# IN-12_Module.net
KiCad netlist of a schematic drawn in EAGLE
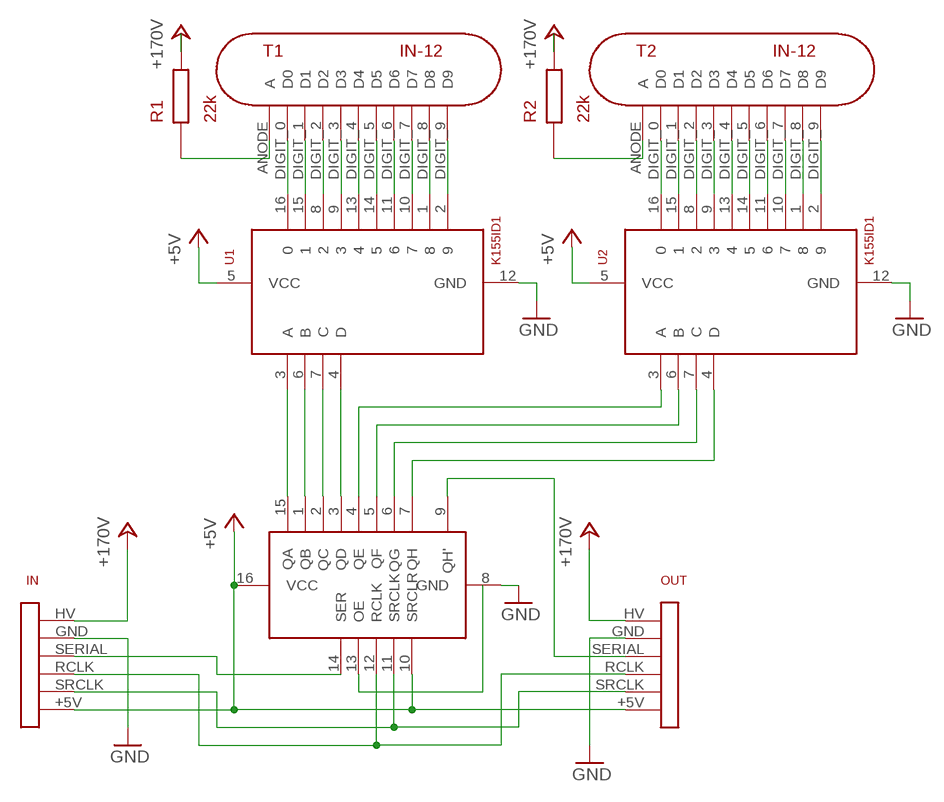
[diagram p0: schematic, sheet 1]

(export (version "E")
  (design (tool "Eeschema 10.0.6"))
  (components
    (comp (ref "IN")
      (value "NIXIE_INTERCONNECT")
      (footprint "eagle-import:NIXIE_INTERCONNECT")
      (libsource (lib "eagle-import") (part "NIXIE_INTERCONNECT"))
    )
    (comp (ref "OUT")
      (value "NIXIE_INTERCONNECT")
      (footprint "eagle-import:NIXIE_INTERCONNECT")
      (libsource (lib "eagle-import") (part "NIXIE_INTERCONNECT"))
    )
    (comp (ref "R1")
      (value "22k")
      (footprint "eagle-import:ANODE_RESISTOR")
      (libsource (lib "eagle-import") (part "ANODE_RESISTOR"))
    )
    (comp (ref "R2")
      (value "22k")
      (footprint "eagle-import:ANODE_RESISTOR")
      (libsource (lib "eagle-import") (part "ANODE_RESISTOR"))
    )
    (comp (ref "T1")
      (value "IN-12")
      (footprint "eagle-import:IN-12")
      (libsource (lib "eagle-import") (part "IN-12"))
    )
    (comp (ref "T2")
      (value "IN-12")
      (footprint "eagle-import:IN-12")
      (libsource (lib "eagle-import") (part "IN-12"))
    )
    (comp (ref "U1")
      (value "K155ID1")
      (footprint "eagle-import:DIP16-2.54-19.2X7.62MM")
      (libsource (lib "eagle-import") (part "K155ID1"))
    )
    (comp (ref "U2")
      (value "K155ID1")
      (footprint "eagle-import:DIP16-2.54-19.2X7.62MM")
      (libsource (lib "eagle-import") (part "K155ID1"))
    )
    (comp (ref "U3")
      (value "74HC595")
      (footprint "eagle-import:DIL16")
      (libsource (lib "eagle-import") (part "74HC595"))
    )
  )
  (nets
    (net (code "1") (name "+5V") (class "Default")
      (node (ref "IN") (pin "+5V") (pinfunction "+5V_+5V") (pintype "bidirectional"))
      (node (ref "OUT") (pin "+5V") (pinfunction "+5V_+5V") (pintype "bidirectional"))
      (node (ref "U1") (pin "5") (pinfunction "VCC_5") (pintype "bidirectional"))
      (node (ref "U2") (pin "5") (pinfunction "VCC_5") (pintype "bidirectional"))
      (node (ref "U3") (pin "10") (pinfunction "SRCLR_10") (pintype "bidirectional"))
      (node (ref "U3") (pin "16") (pinfunction "VCC_16") (pintype "bidirectional"))
    )
    (net (code "2") (name "+170V") (class "Default")
      (node (ref "IN") (pin "HV") (pinfunction "HV_HV") (pintype "bidirectional"))
      (node (ref "OUT") (pin "HV") (pinfunction "HV_HV") (pintype "bidirectional"))
      (node (ref "R1") (pin "P$2") (pinfunction "P$2_P$2") (pintype "bidirectional"))
      (node (ref "R2") (pin "P$2") (pinfunction "P$2_P$2") (pintype "bidirectional"))
    )
    (net (code "3") (name "GND") (class "Default")
      (node (ref "IN") (pin "GND") (pinfunction "GND_GND") (pintype "bidirectional"))
      (node (ref "OUT") (pin "GND") (pinfunction "GND_GND") (pintype "bidirectional"))
      (node (ref "U1") (pin "12") (pinfunction "GND_12") (pintype "bidirectional"))
      (node (ref "U2") (pin "12") (pinfunction "GND_12") (pintype "bidirectional"))
      (node (ref "U3") (pin "8") (pinfunction "GND_8") (pintype "bidirectional"))
    )
    (net (code "4") (name "Net-(T1-A)") (class "Default")
      (node (ref "R1") (pin "P$1") (pinfunction "P$1_P$1") (pintype "bidirectional"))
      (node (ref "T1") (pin "ANODE") (pinfunction "A_ANODE") (pintype "bidirectional"))
    )
    (net (code "5") (name "Net-(T1-D0)") (class "Default")
      (node (ref "T1") (pin "DIGIT_0") (pinfunction "D0_DIGIT_0") (pintype "bidirectional"))
      (node (ref "U1") (pin "16") (pinfunction "0_16") (pintype "bidirectional"))
    )
    (net (code "6") (name "Net-(T1-D1)") (class "Default")
      (node (ref "T1") (pin "DIGIT_1") (pinfunction "D1_DIGIT_1") (pintype "bidirectional"))
      (node (ref "U1") (pin "15") (pinfunction "1_15") (pintype "bidirectional"))
    )
    (net (code "7") (name "Net-(T1-D2)") (class "Default")
      (node (ref "T1") (pin "DIGIT_2") (pinfunction "D2_DIGIT_2") (pintype "bidirectional"))
      (node (ref "U1") (pin "8") (pinfunction "2_8") (pintype "bidirectional"))
    )
    (net (code "8") (name "Net-(T1-D3)") (class "Default")
      (node (ref "T1") (pin "DIGIT_3") (pinfunction "D3_DIGIT_3") (pintype "bidirectional"))
      (node (ref "U1") (pin "9") (pinfunction "3_9") (pintype "bidirectional"))
    )
    (net (code "9") (name "Net-(T1-D4)") (class "Default")
      (node (ref "T1") (pin "DIGIT_4") (pinfunction "D4_DIGIT_4") (pintype "bidirectional"))
      (node (ref "U1") (pin "13") (pinfunction "4_13") (pintype "bidirectional"))
    )
    (net (code "10") (name "Net-(T1-D5)") (class "Default")
      (node (ref "T1") (pin "DIGIT_5") (pinfunction "D5_DIGIT_5") (pintype "bidirectional"))
      (node (ref "U1") (pin "14") (pinfunction "5_14") (pintype "bidirectional"))
    )
    (net (code "11") (name "Net-(T1-D6)") (class "Default")
      (node (ref "T1") (pin "DIGIT_6") (pinfunction "D6_DIGIT_6") (pintype "bidirectional"))
      (node (ref "U1") (pin "11") (pinfunction "6_11") (pintype "bidirectional"))
    )
    (net (code "12") (name "Net-(T1-D7)") (class "Default")
      (node (ref "T1") (pin "DIGIT_7") (pinfunction "D7_DIGIT_7") (pintype "bidirectional"))
      (node (ref "U1") (pin "10") (pinfunction "7_10") (pintype "bidirectional"))
    )
    (net (code "13") (name "Net-(T1-D8)") (class "Default")
      (node (ref "T1") (pin "DIGIT_8") (pinfunction "D8_DIGIT_8") (pintype "bidirectional"))
      (node (ref "U1") (pin "1") (pinfunction "8_1") (pintype "bidirectional"))
    )
    (net (code "14") (name "Net-(T1-D9)") (class "Default")
      (node (ref "T1") (pin "DIGIT_9") (pinfunction "D9_DIGIT_9") (pintype "bidirectional"))
      (node (ref "U1") (pin "2") (pinfunction "9_2") (pintype "bidirectional"))
    )
    (net (code "15") (name "Net-(T2-A)") (class "Default")
      (node (ref "R2") (pin "P$1") (pinfunction "P$1_P$1") (pintype "bidirectional"))
      (node (ref "T2") (pin "ANODE") (pinfunction "A_ANODE") (pintype "bidirectional"))
    )
    (net (code "16") (name "Net-(T2-D0)") (class "Default")
      (node (ref "T2") (pin "DIGIT_0") (pinfunction "D0_DIGIT_0") (pintype "bidirectional"))
      (node (ref "U2") (pin "16") (pinfunction "0_16") (pintype "bidirectional"))
    )
    (net (code "17") (name "Net-(T2-D1)") (class "Default")
      (node (ref "T2") (pin "DIGIT_1") (pinfunction "D1_DIGIT_1") (pintype "bidirectional"))
      (node (ref "U2") (pin "15") (pinfunction "1_15") (pintype "bidirectional"))
    )
    (net (code "18") (name "Net-(T2-D2)") (class "Default")
      (node (ref "T2") (pin "DIGIT_2") (pinfunction "D2_DIGIT_2") (pintype "bidirectional"))
      (node (ref "U2") (pin "8") (pinfunction "2_8") (pintype "bidirectional"))
    )
    (net (code "19") (name "Net-(T2-D3)") (class "Default")
      (node (ref "T2") (pin "DIGIT_3") (pinfunction "D3_DIGIT_3") (pintype "bidirectional"))
      (node (ref "U2") (pin "9") (pinfunction "3_9") (pintype "bidirectional"))
    )
    (net (code "20") (name "Net-(T2-D4)") (class "Default")
      (node (ref "T2") (pin "DIGIT_4") (pinfunction "D4_DIGIT_4") (pintype "bidirectional"))
      (node (ref "U2") (pin "13") (pinfunction "4_13") (pintype "bidirectional"))
    )
    (net (code "21") (name "Net-(T2-D5)") (class "Default")
      (node (ref "T2") (pin "DIGIT_5") (pinfunction "D5_DIGIT_5") (pintype "bidirectional"))
      (node (ref "U2") (pin "14") (pinfunction "5_14") (pintype "bidirectional"))
    )
    (net (code "22") (name "Net-(T2-D6)") (class "Default")
      (node (ref "T2") (pin "DIGIT_6") (pinfunction "D6_DIGIT_6") (pintype "bidirectional"))
      (node (ref "U2") (pin "11") (pinfunction "6_11") (pintype "bidirectional"))
    )
    (net (code "23") (name "Net-(T2-D7)") (class "Default")
      (node (ref "T2") (pin "DIGIT_7") (pinfunction "D7_DIGIT_7") (pintype "bidirectional"))
      (node (ref "U2") (pin "10") (pinfunction "7_10") (pintype "bidirectional"))
    )
    (net (code "24") (name "Net-(T2-D8)") (class "Default")
      (node (ref "T2") (pin "DIGIT_8") (pinfunction "D8_DIGIT_8") (pintype "bidirectional"))
      (node (ref "U2") (pin "1") (pinfunction "8_1") (pintype "bidirectional"))
    )
    (net (code "25") (name "Net-(T2-D9)") (class "Default")
      (node (ref "T2") (pin "DIGIT_9") (pinfunction "D9_DIGIT_9") (pintype "bidirectional"))
      (node (ref "U2") (pin "2") (pinfunction "9_2") (pintype "bidirectional"))
    )
    (net (code "26") (name "Net-(U1-A)") (class "Default")
      (node (ref "U1") (pin "3") (pinfunction "A_3") (pintype "bidirectional"))
      (node (ref "U3") (pin "15") (pinfunction "QA_15") (pintype "bidirectional"))
    )
    (net (code "27") (name "Net-(U1-B)") (class "Default")
      (node (ref "U1") (pin "6") (pinfunction "B_6") (pintype "bidirectional"))
      (node (ref "U3") (pin "1") (pinfunction "QB_1") (pintype "bidirectional"))
    )
    (net (code "28") (name "Net-(U1-C)") (class "Default")
      (node (ref "U1") (pin "7") (pinfunction "C_7") (pintype "bidirectional"))
      (node (ref "U3") (pin "2") (pinfunction "QC_2") (pintype "bidirectional"))
    )
    (net (code "29") (name "Net-(U1-D)") (class "Default")
      (node (ref "U1") (pin "4") (pinfunction "D_4") (pintype "bidirectional"))
      (node (ref "U3") (pin "3") (pinfunction "QD_3") (pintype "bidirectional"))
    )
    (net (code "30") (name "Net-(U2-A)") (class "Default")
      (node (ref "U2") (pin "3") (pinfunction "A_3") (pintype "bidirectional"))
      (node (ref "U3") (pin "4") (pinfunction "QE_4") (pintype "bidirectional"))
    )
    (net (code "31") (name "Net-(U2-B)") (class "Default")
      (node (ref "U2") (pin "6") (pinfunction "B_6") (pintype "bidirectional"))
      (node (ref "U3") (pin "5") (pinfunction "QF_5") (pintype "bidirectional"))
    )
    (net (code "32") (name "Net-(U2-C)") (class "Default")
      (node (ref "U2") (pin "7") (pinfunction "C_7") (pintype "bidirectional"))
      (node (ref "U3") (pin "6") (pinfunction "QG_6") (pintype "bidirectional"))
    )
    (net (code "33") (name "Net-(U2-D)") (class "Default")
      (node (ref "U2") (pin "4") (pinfunction "D_4") (pintype "bidirectional"))
      (node (ref "U3") (pin "7") (pinfunction "QH_7") (pintype "bidirectional"))
    )
    (net (code "34") (name "Net-(U3-QH')") (class "Default")
      (node (ref "OUT") (pin "SERIAL") (pinfunction "SERIAL_SERIAL") (pintype "bidirectional"))
      (node (ref "U3") (pin "9") (pinfunction "QH'_9") (pintype "bidirectional"))
    )
    (net (code "35") (name "Net-(U3-RCLK)") (class "Default")
      (node (ref "IN") (pin "RCLK") (pinfunction "RCLK_RCLK") (pintype "bidirectional"))
      (node (ref "OUT") (pin "RCLK") (pinfunction "RCLK_RCLK") (pintype "bidirectional"))
      (node (ref "U3") (pin "12") (pinfunction "RCLK_12") (pintype "bidirectional"))
    )
    (net (code "36") (name "Net-(U3-SER)") (class "Default")
      (node (ref "IN") (pin "SERIAL") (pinfunction "SERIAL_SERIAL") (pintype "bidirectional"))
      (node (ref "U3") (pin "14") (pinfunction "SER_14") (pintype "bidirectional"))
    )
    (net (code "37") (name "Net-(U3-SRCLK)") (class "Default")
      (node (ref "IN") (pin "SRCLK") (pinfunction "SRCLK_SRCLK") (pintype "bidirectional"))
      (node (ref "OUT") (pin "SRCLK") (pinfunction "SRCLK_SRCLK") (pintype "bidirectional"))
      (node (ref "U3") (pin "11") (pinfunction "SRCLK_11") (pintype "bidirectional"))
    )
    (net (code "38") (name "unconnected-(U3-OE-Pad13)") (class "Default")
      (node (ref "U3") (pin "13") (pinfunction "OE_13") (pintype "bidirectional"))
    )
  )
)
